# LM2596_SMD_0603.net
KiCad netlist of a schematic drawn in EAGLE
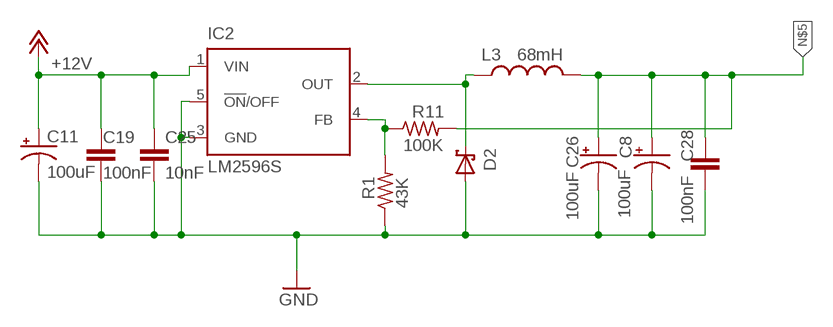
[diagram p0: schematic, sheet 1]

(export (version "E")
  (design (tool "Eeschema 10.0.6"))
  (components
    (comp (ref "C8")
      (value "100uF")
      (footprint "eagle-import:UD-6,3X7,7_NICHICON")
      (libsource (lib "eagle-import") (part "CPOL-USUD-6,3X7,7"))
    )
    (comp (ref "C11")
      (value "100uF")
      (footprint "eagle-import:UD-6,3X7,7_NICHICON")
      (libsource (lib "eagle-import") (part "CPOL-USUD-6,3X7,7"))
    )
    (comp (ref "C19")
      (value "100nF")
      (footprint "eagle-import:C0603")
      (libsource (lib "eagle-import") (part "C-EUC0603"))
    )
    (comp (ref "C25")
      (value "10nF")
      (footprint "eagle-import:C0603")
      (libsource (lib "eagle-import") (part "C-EUC0603"))
    )
    (comp (ref "C26")
      (value "100uF")
      (footprint "eagle-import:UD-6,3X7,7_NICHICON")
      (libsource (lib "eagle-import") (part "CPOL-USUD-6,3X7,7"))
    )
    (comp (ref "C28")
      (value "100nF")
      (footprint "eagle-import:C0603")
      (libsource (lib "eagle-import") (part "C-EUC0603"))
    )
    (comp (ref "D2")
      (value "SCHOTTKY-DIODEDO41")
      (footprint "eagle-import:DO41-10")
      (libsource (lib "eagle-import") (part "SCHOTTKY-DIODEDO41"))
    )
    (comp (ref "IC2")
      (value "LM2596S")
      (footprint "eagle-import:TO263-5")
      (fields (field (name "MF") "NATIONAL SEMICONDUCTOR") (field (name "MPN") "LM2596S-ADJ/NOPB"))
      (libsource (lib "eagle-import") (part "LM2596S"))
    )
    (comp (ref "L3")
      (value "68mH")
      (footprint "eagle-import:L0603")
      (libsource (lib "eagle-import") (part "L-USL0603"))
    )
    (comp (ref "R1")
      (value "43K")
      (footprint "eagle-import:R0603")
      (libsource (lib "eagle-import") (part "R-US_R0603"))
    )
    (comp (ref "R11")
      (value "100K")
      (footprint "eagle-import:R0603")
      (libsource (lib "eagle-import") (part "R-US_R0603"))
    )
  )
  (nets
    (net (code "1") (name "+12V") (class "Default")
      (node (ref "C11") (pin "+") (pinfunction "+_+") (pintype "passive"))
      (node (ref "C19") (pin "1") (pinfunction "1_1") (pintype "passive"))
      (node (ref "C25") (pin "1") (pinfunction "1_1") (pintype "passive"))
      (node (ref "IC2") (pin "1") (pinfunction "VIN_1") (pintype "input"))
    )
    (net (code "2") (name "GND") (class "Default")
      (node (ref "C11") (pin "-") (pinfunction "-_-") (pintype "passive"))
      (node (ref "C19") (pin "2") (pinfunction "2_2") (pintype "passive"))
      (node (ref "C25") (pin "2") (pinfunction "2_2") (pintype "passive"))
      (node (ref "C26") (pin "-") (pinfunction "-_-") (pintype "passive"))
      (node (ref "C28") (pin "2") (pinfunction "2_2") (pintype "passive"))
      (node (ref "C8") (pin "-") (pinfunction "-_-") (pintype "passive"))
      (node (ref "D2") (pin "A") (pinfunction "A_A") (pintype "passive"))
      (node (ref "IC2") (pin "3") (pinfunction "GND_3") (pintype "power_in"))
      (node (ref "IC2") (pin "5") (pinfunction "~{ON}/OFF_5") (pintype "input"))
      (node (ref "R1") (pin "1") (pinfunction "1_1") (pintype "passive"))
    )
    (net (code "3") (name "N$5") (class "Default")
      (node (ref "C26") (pin "+") (pinfunction "+_+") (pintype "passive"))
      (node (ref "C28") (pin "1") (pinfunction "1_1") (pintype "passive"))
      (node (ref "C8") (pin "+") (pinfunction "+_+") (pintype "passive"))
      (node (ref "L3") (pin "2") (pinfunction "2_2") (pintype "passive"))
      (node (ref "R11") (pin "2") (pinfunction "2_2") (pintype "passive"))
    )
    (net (code "4") (name "Net-(IC2-FB)") (class "Default")
      (node (ref "IC2") (pin "4") (pinfunction "FB_4") (pintype "input"))
      (node (ref "R1") (pin "2") (pinfunction "2_2") (pintype "passive"))
      (node (ref "R11") (pin "1") (pinfunction "1_1") (pintype "passive"))
    )
    (net (code "5") (name "Net-(IC2-OUT)") (class "Default")
      (node (ref "D2") (pin "C") (pinfunction "C_C") (pintype "passive"))
      (node (ref "IC2") (pin "2") (pinfunction "OUT_2") (pintype "output"))
      (node (ref "L3") (pin "1") (pinfunction "1_1") (pintype "passive"))
    )
  )
)
